# F1C100s.net
KiCad netlist of a schematic drawn in Altium Designer
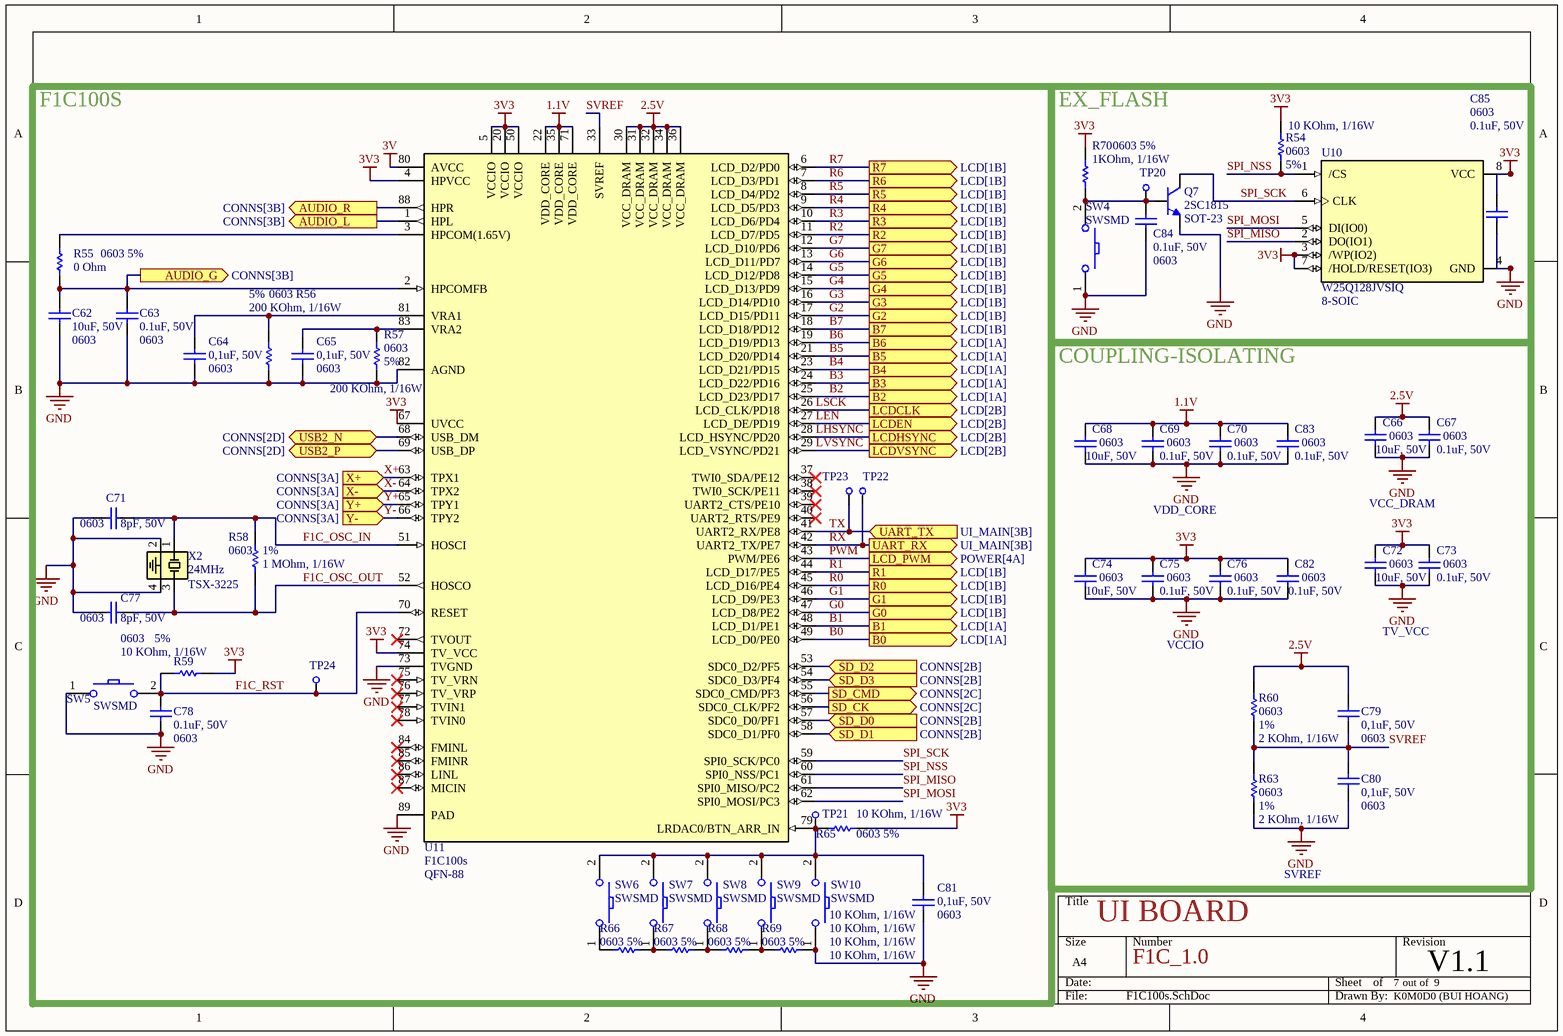
[diagram p0: F1C100s.SchDoc]

(export (version "E")
  (design (tool "Eeschema 10.0.6"))
  (components
    (comp (ref "C62")
      (value "10uF, 50V")
      (footprint "C_0603")
      (description "CAP_0603")
      (fields (field (name "PACKAGE") "0603"))
      (libsource (lib "DisplayLib") (part "CAP_0603"))
    )
    (comp (ref "C63")
      (value "0.1uF, 50V")
      (footprint "C_0603")
      (description "CAP_0603")
      (fields (field (name "PACKAGE") "0603"))
      (libsource (lib "DisplayLib") (part "CAP_0603"))
    )
    (comp (ref "C64")
      (value "0,1uF, 50V")
      (footprint "C_0603")
      (description "CAP_0603")
      (fields (field (name "PACKAGE") "0603"))
      (libsource (lib "DisplayLib") (part "CAP_0603"))
    )
    (comp (ref "C65")
      (value "0,1uF, 50V")
      (footprint "C_0603")
      (description "CAP_0603")
      (fields (field (name "PACKAGE") "0603"))
      (libsource (lib "DisplayLib") (part "CAP_0603"))
    )
    (comp (ref "C66")
      (value "10uF, 50V")
      (footprint "C_0603")
      (description "CAP_0603")
      (fields (field (name "PACKAGE") "0603"))
      (libsource (lib "DisplayLib") (part "CAP_0603"))
    )
    (comp (ref "C67")
      (value "0.1uF, 50V")
      (footprint "C_0603")
      (description "CAP_0603")
      (fields (field (name "PACKAGE") "0603"))
      (libsource (lib "DisplayLib") (part "CAP_0603"))
    )
    (comp (ref "C68")
      (value "10uF, 50V")
      (footprint "C_0603")
      (description "CAP_0603")
      (fields (field (name "PACKAGE") "0603"))
      (libsource (lib "DisplayLib") (part "CAP_0603"))
    )
    (comp (ref "C69")
      (value "0.1uF, 50V")
      (footprint "C_0603")
      (description "CAP_0603")
      (fields (field (name "PACKAGE") "0603"))
      (libsource (lib "DisplayLib") (part "CAP_0603"))
    )
    (comp (ref "C70")
      (value "0.1uF, 50V")
      (footprint "C_0603")
      (description "CAP_0603")
      (fields (field (name "PACKAGE") "0603"))
      (libsource (lib "DisplayLib") (part "CAP_0603"))
    )
    (comp (ref "C71")
      (value "8pF, 50V")
      (footprint "C_0603")
      (description "CAP_0603")
      (fields (field (name "PACKAGE") "0603"))
      (libsource (lib "DisplayLib") (part "CAP_0603"))
    )
    (comp (ref "C72")
      (value "10uF, 50V")
      (footprint "C_0603")
      (description "CAP_0603")
      (fields (field (name "PACKAGE") "0603"))
      (libsource (lib "DisplayLib") (part "CAP_0603"))
    )
    (comp (ref "C73")
      (value "0.1uF, 50V")
      (footprint "C_0603")
      (description "CAP_0603")
      (fields (field (name "PACKAGE") "0603"))
      (libsource (lib "DisplayLib") (part "CAP_0603"))
    )
    (comp (ref "C74")
      (value "10uF, 50V")
      (footprint "C_0603")
      (description "CAP_0603")
      (fields (field (name "PACKAGE") "0603"))
      (libsource (lib "DisplayLib") (part "CAP_0603"))
    )
    (comp (ref "C75")
      (value "0.1uF, 50V")
      (footprint "C_0603")
      (description "CAP_0603")
      (fields (field (name "PACKAGE") "0603"))
      (libsource (lib "DisplayLib") (part "CAP_0603"))
    )
    (comp (ref "C76")
      (value "0.1uF, 50V")
      (footprint "C_0603")
      (description "CAP_0603")
      (fields (field (name "PACKAGE") "0603"))
      (libsource (lib "DisplayLib") (part "CAP_0603"))
    )
    (comp (ref "C77")
      (value "8pF, 50V")
      (footprint "C_0603")
      (description "CAP_0603")
      (fields (field (name "PACKAGE") "0603"))
      (libsource (lib "DisplayLib") (part "CAP_0603"))
    )
    (comp (ref "C78")
      (value "0.1uF, 50V")
      (footprint "C_0603")
      (description "CAP_0603")
      (fields (field (name "PACKAGE") "0603"))
      (libsource (lib "DisplayLib") (part "CAP_0603"))
    )
    (comp (ref "C79")
      (value "0,1uF, 50V")
      (footprint "C_0603")
      (description "CAP_0603")
      (fields (field (name "PACKAGE") "0603"))
      (libsource (lib "DisplayLib") (part "CAP_0603"))
    )
    (comp (ref "C80")
      (value "0,1uF, 50V")
      (footprint "C_0603")
      (description "CAP_0603")
      (fields (field (name "PACKAGE") "0603"))
      (libsource (lib "DisplayLib") (part "CAP_0603"))
    )
    (comp (ref "C81")
      (value "0,1uF, 50V")
      (footprint "C_0603")
      (description "CAP_0603")
      (fields (field (name "PACKAGE") "0603"))
      (libsource (lib "DisplayLib") (part "CAP_0603"))
    )
    (comp (ref "C82")
      (value "0.1uF, 50V")
      (footprint "C_0603")
      (description "CAP_0603")
      (fields (field (name "PACKAGE") "0603"))
      (libsource (lib "DisplayLib") (part "CAP_0603"))
    )
    (comp (ref "C83")
      (value "0.1uF, 50V")
      (footprint "C_0603")
      (description "CAP_0603")
      (fields (field (name "PACKAGE") "0603"))
      (libsource (lib "DisplayLib") (part "CAP_0603"))
    )
    (comp (ref "C84")
      (value "0.1uF, 50V")
      (footprint "C_0603")
      (description "CAP_0603")
      (fields (field (name "PACKAGE") "0603"))
      (libsource (lib "DisplayLib") (part "CAP_0603"))
    )
    (comp (ref "C85")
      (value "0.1uF, 50V")
      (footprint "C_0603")
      (description "CAP_0603")
      (fields (field (name "PACKAGE") "0603"))
      (libsource (lib "DisplayLib") (part "CAP_0603"))
    )
    (comp (ref "Q7")
      (value "2SC1815")
      (footprint "PKG_SOT-23")
      (description "HF Transistor NPN")
      (fields (field (name "PACKAGE") "SOT-23"))
      (libsource (lib "DisplayLib") (part "2SC1815"))
    )
    (comp (ref "R54")
      (value "10 KOhm, 1/16W")
      (footprint "R_0603")
      (description "RES_0603")
      (fields (field (name "PACKAGE") "0603") (field (name "ACC") "5%"))
      (libsource (lib "DisplayLib") (part "RES_0603"))
    )
    (comp (ref "R55")
      (value "0 Ohm")
      (footprint "R_0603")
      (description "RES_0603")
      (fields (field (name "PACKAGE") "0603") (field (name "ACC") "5%"))
      (libsource (lib "DisplayLib") (part "RES_0603"))
    )
    (comp (ref "R56")
      (value "200 KOhm, 1/16W")
      (footprint "R_0603")
      (description "RES_0603")
      (fields (field (name "PACKAGE") "0603") (field (name "ACC") "5%"))
      (libsource (lib "DisplayLib") (part "RES_0603"))
    )
    (comp (ref "R57")
      (value "200 KOhm, 1/16W")
      (footprint "R_0603")
      (description "RES_0603")
      (fields (field (name "PACKAGE") "0603") (field (name "ACC") "5%"))
      (libsource (lib "DisplayLib") (part "RES_0603"))
    )
    (comp (ref "R58")
      (value "1 MOhm, 1/16W")
      (footprint "R_0603")
      (description "RES_0603")
      (fields (field (name "PACKAGE") "0603") (field (name "ACC") "1%"))
      (libsource (lib "DisplayLib") (part "RES_0603"))
    )
    (comp (ref "R59")
      (value "10 KOhm, 1/16W")
      (footprint "R_0603")
      (description "RES_0603")
      (fields (field (name "PACKAGE") "0603") (field (name "ACC") "5%"))
      (libsource (lib "DisplayLib") (part "RES_0603"))
    )
    (comp (ref "R60")
      (value "2 KOhm, 1/16W")
      (footprint "R_0603")
      (description "RES_0603")
      (fields (field (name "PACKAGE") "0603") (field (name "ACC") "1%"))
      (libsource (lib "DisplayLib") (part "RES_0603"))
    )
    (comp (ref "R63")
      (value "2 KOhm, 1/16W")
      (footprint "R_0603")
      (description "RES_0603")
      (fields (field (name "PACKAGE") "0603") (field (name "ACC") "1%"))
      (libsource (lib "DisplayLib") (part "RES_0603"))
    )
    (comp (ref "R65")
      (value "10 KOhm, 1/16W")
      (footprint "R_0603")
      (description "RES_0603")
      (fields (field (name "PACKAGE") "0603") (field (name "ACC") "5%"))
      (libsource (lib "DisplayLib") (part "RES_0603"))
    )
    (comp (ref "R66")
      (value "10 KOhm, 1/16W")
      (footprint "R_0603")
      (description "RES_0603")
      (fields (field (name "PACKAGE") "0603") (field (name "ACC") "5%"))
      (libsource (lib "DisplayLib") (part "RES_0603"))
    )
    (comp (ref "R67")
      (value "10 KOhm, 1/16W")
      (footprint "R_0603")
      (description "RES_0603")
      (fields (field (name "PACKAGE") "0603") (field (name "ACC") "5%"))
      (libsource (lib "DisplayLib") (part "RES_0603"))
    )
    (comp (ref "R68")
      (value "10 KOhm, 1/16W")
      (footprint "R_0603")
      (description "RES_0603")
      (fields (field (name "PACKAGE") "0603") (field (name "ACC") "5%"))
      (libsource (lib "DisplayLib") (part "RES_0603"))
    )
    (comp (ref "R69")
      (value "10 KOhm, 1/16W")
      (footprint "R_0603")
      (description "RES_0603")
      (fields (field (name "PACKAGE") "0603") (field (name "ACC") "5%"))
      (libsource (lib "DisplayLib") (part "RES_0603"))
    )
    (comp (ref "R70")
      (value "1KOhm, 1/16W")
      (footprint "R_0603")
      (description "RES_0603")
      (fields (field (name "PACKAGE") "0603") (field (name "ACC") "5%"))
      (libsource (lib "DisplayLib") (part "RES_0603"))
    )
    (comp (ref "SW4")
      (value "SWSMD")
      (footprint "SW_SMD_NOGND")
      (description "SW_SMD")
      (libsource (lib "DisplayLib") (part "SWSMD_NOGND"))
    )
    (comp (ref "SW5")
      (value "SWSMD")
      (footprint "SW_SMD_NOGND")
      (description "SW_SMD")
      (libsource (lib "") (part "SWSMD_NOGND_1"))
    )
    (comp (ref "SW6")
      (value "SWSMD")
      (footprint "SW_SMD_NOGND")
      (description "SW_SMD")
      (libsource (lib "DisplayLib") (part "SWSMD_NOGND"))
    )
    (comp (ref "SW7")
      (value "SWSMD")
      (footprint "SW_SMD_NOGND")
      (description "SW_SMD")
      (libsource (lib "DisplayLib") (part "SWSMD_NOGND"))
    )
    (comp (ref "SW8")
      (value "SWSMD")
      (footprint "SW_SMD_NOGND")
      (description "SW_SMD")
      (libsource (lib "DisplayLib") (part "SWSMD_NOGND"))
    )
    (comp (ref "SW9")
      (value "SWSMD")
      (footprint "SW_SMD_NOGND")
      (description "SW_SMD")
      (libsource (lib "DisplayLib") (part "SWSMD_NOGND"))
    )
    (comp (ref "SW10")
      (value "SWSMD")
      (footprint "SW_SMD_NOGND")
      (description "SW_SMD")
      (libsource (lib "DisplayLib") (part "SWSMD_NOGND"))
    )
    (comp (ref "TP20")
      (value "TESTPT")
      (footprint "TESTPT")
      (description "Test point")
      (libsource (lib "DisplayLib") (part "TESTPT"))
    )
    (comp (ref "TP21")
      (value "TESTPT")
      (footprint "TESTPT")
      (description "Test point")
      (libsource (lib "DisplayLib") (part "TESTPT"))
    )
    (comp (ref "TP22")
      (value "TESTPT")
      (footprint "TESTPT")
      (description "Test point")
      (libsource (lib "DisplayLib") (part "TESTPT"))
    )
    (comp (ref "TP23")
      (value "TESTPT")
      (footprint "TESTPT")
      (description "Test point")
      (libsource (lib "DisplayLib") (part "TESTPT"))
    )
    (comp (ref "TP24")
      (value "TESTPT")
      (footprint "TESTPT")
      (description "Test point")
      (libsource (lib "DisplayLib") (part "TESTPT"))
    )
    (comp (ref "U10")
      (value "W25Q128JVSIQ")
      (footprint "PKG_8-SOIC")
      (description "FLASH - NOR Memory IC 128Mb (16M x 8) SPI - Quad I/O, QPI, DTR 133 MHz 8-SOIC")
      (fields (field (name "PACKAGE") "8-SOIC"))
      (libsource (lib "DisplayLib") (part "W25Q128JVSIQ"))
    )
    (comp (ref "U11")
      (value "F1C100s")
      (footprint "PKG_QFN-88")
      (fields (field (name "PACKAGE") "QFN-88"))
      (libsource (lib "DisplayLib") (part "F1C100s"))
    )
    (comp (ref "X2")
      (value "24MHz")
      (footprint "PKG_TSX-3225")
      (description "Crystal, 24 MHz, -30 to 85 degC, 3.2 x 2.5 x 0.9 mm SMD")
      (fields (field (name "PACKAGE") "TSX-3225"))
      (libsource (lib "DisplayLib") (part "XTAL"))
    )
  )
  (nets
    (net (code "1") (name "/AUDIO_G") (class "Default")
      (node (ref "C62") (pin "2") (pinfunction "2_2") (pintype "passive"))
      (node (ref "C63") (pin "2") (pinfunction "2_2") (pintype "passive"))
      (node (ref "R55") (pin "1") (pinfunction "1_1") (pintype "passive"))
      (node (ref "U11") (pin "2") (pinfunction "HPCOMFB_2") (pintype "input"))
    )
    (net (code "2") (name "/AUDIO_L") (class "Default")
      (node (ref "U11") (pin "1") (pinfunction "HPL_1") (pintype "output"))
    )
    (net (code "3") (name "/AUDIO_R") (class "Default")
      (node (ref "U11") (pin "88") (pinfunction "HPR_88") (pintype "output"))
    )
    (net (code "4") (name "/B0") (class "Default")
      (node (ref "U11") (pin "49") (pinfunction "LCD_D0/PE0_49") (pintype "bidirectional"))
    )
    (net (code "5") (name "/B1") (class "Default")
      (node (ref "U11") (pin "48") (pinfunction "LCD_D1/PE1_48") (pintype "bidirectional"))
    )
    (net (code "6") (name "/B2") (class "Default")
      (node (ref "U11") (pin "25") (pinfunction "LCD_D23/PD17_25") (pintype "bidirectional"))
    )
    (net (code "7") (name "/B3") (class "Default")
      (node (ref "U11") (pin "24") (pinfunction "LCD_D22/PD16_24") (pintype "bidirectional"))
    )
    (net (code "8") (name "/B4") (class "Default")
      (node (ref "U11") (pin "23") (pinfunction "LCD_D21/PD15_23") (pintype "bidirectional"))
    )
    (net (code "9") (name "/B5") (class "Default")
      (node (ref "U11") (pin "21") (pinfunction "LCD_D20/PD14_21") (pintype "bidirectional"))
    )
    (net (code "10") (name "/B6") (class "Default")
      (node (ref "U11") (pin "19") (pinfunction "LCD_D19/PD13_19") (pintype "bidirectional"))
    )
    (net (code "11") (name "/B7") (class "Default")
      (node (ref "U11") (pin "18") (pinfunction "LCD_D18/PD12_18") (pintype "bidirectional"))
    )
    (net (code "12") (name "/F1C_OSC_IN") (class "Default")
      (node (ref "C71") (pin "2") (pinfunction "2_2") (pintype "passive"))
      (node (ref "R58") (pin "2") (pinfunction "2_2") (pintype "passive"))
      (node (ref "U11") (pin "51") (pinfunction "HOSCI_51") (pintype "input"))
      (node (ref "X2") (pin "1") (pinfunction "1_1") (pintype "passive"))
    )
    (net (code "13") (name "/F1C_OSC_OUT") (class "Default")
      (node (ref "C77") (pin "2") (pinfunction "2_2") (pintype "passive"))
      (node (ref "R58") (pin "1") (pinfunction "1_1") (pintype "passive"))
      (node (ref "U11") (pin "52") (pinfunction "HOSCO_52") (pintype "output"))
      (node (ref "X2") (pin "3") (pinfunction "3_3") (pintype "passive"))
    )
    (net (code "14") (name "/F1C_RST") (class "Default")
      (node (ref "C78") (pin "2") (pinfunction "2_2") (pintype "passive"))
      (node (ref "R59") (pin "1") (pinfunction "1_1") (pintype "passive"))
      (node (ref "SW5") (pin "2") (pinfunction "2_2") (pintype "passive"))
      (node (ref "TP24") (pin "1") (pinfunction "1_1") (pintype "passive"))
      (node (ref "U11") (pin "70") (pinfunction "RESET_70") (pintype "bidirectional"))
    )
    (net (code "15") (name "/G0") (class "Default")
      (node (ref "U11") (pin "47") (pinfunction "LCD_D8/PE2_47") (pintype "bidirectional"))
    )
    (net (code "16") (name "/G1") (class "Default")
      (node (ref "U11") (pin "46") (pinfunction "LCD_D9/PE3_46") (pintype "bidirectional"))
    )
    (net (code "17") (name "/G2") (class "Default")
      (node (ref "U11") (pin "17") (pinfunction "LCD_D15/PD11_17") (pintype "bidirectional"))
    )
    (net (code "18") (name "/G3") (class "Default")
      (node (ref "U11") (pin "16") (pinfunction "LCD_D14/PD10_16") (pintype "bidirectional"))
    )
    (net (code "19") (name "/G4") (class "Default")
      (node (ref "U11") (pin "15") (pinfunction "LCD_D13/PD9_15") (pintype "bidirectional"))
    )
    (net (code "20") (name "/G5") (class "Default")
      (node (ref "U11") (pin "14") (pinfunction "LCD_D12/PD8_14") (pintype "bidirectional"))
    )
    (net (code "21") (name "/G6") (class "Default")
      (node (ref "U11") (pin "13") (pinfunction "LCD_D11/PD7_13") (pintype "bidirectional"))
    )
    (net (code "22") (name "/G7") (class "Default")
      (node (ref "U11") (pin "12") (pinfunction "LCD_D10/PD6_12") (pintype "bidirectional"))
    )
    (net (code "23") (name "/LEN") (class "Default")
      (node (ref "U11") (pin "27") (pinfunction "LCD_DE/PD19_27") (pintype "bidirectional"))
    )
    (net (code "24") (name "/LHSYNC") (class "Default")
      (node (ref "U11") (pin "28") (pinfunction "LCD_HSYNC/PD20_28") (pintype "bidirectional"))
    )
    (net (code "25") (name "/LSCK") (class "Default")
      (node (ref "U11") (pin "26") (pinfunction "LCD_CLK/PD18_26") (pintype "bidirectional"))
    )
    (net (code "26") (name "/LVSYNC") (class "Default")
      (node (ref "U11") (pin "29") (pinfunction "LCD_VSYNC/PD21_29") (pintype "bidirectional"))
    )
    (net (code "27") (name "/PWM") (class "Default")
      (node (ref "U11") (pin "43") (pinfunction "PWM/PE6_43") (pintype "bidirectional"))
    )
    (net (code "28") (name "/R0") (class "Default")
      (node (ref "U11") (pin "45") (pinfunction "LCD_D16/PE4_45") (pintype "bidirectional"))
    )
    (net (code "29") (name "/R1") (class "Default")
      (node (ref "U11") (pin "44") (pinfunction "LCD_D17/PE5_44") (pintype "bidirectional"))
    )
    (net (code "30") (name "/R2") (class "Default")
      (node (ref "U11") (pin "11") (pinfunction "LCD_D7/PD5_11") (pintype "bidirectional"))
    )
    (net (code "31") (name "/R3") (class "Default")
      (node (ref "U11") (pin "10") (pinfunction "LCD_D6/PD4_10") (pintype "bidirectional"))
    )
    (net (code "32") (name "/R4") (class "Default")
      (node (ref "U11") (pin "9") (pinfunction "LCD_D5/PD3_9") (pintype "bidirectional"))
    )
    (net (code "33") (name "/R5") (class "Default")
      (node (ref "U11") (pin "8") (pinfunction "LCD_D4/PD2_8") (pintype "bidirectional"))
    )
    (net (code "34") (name "/R6") (class "Default")
      (node (ref "U11") (pin "7") (pinfunction "LCD_D3/PD1_7") (pintype "bidirectional"))
    )
    (net (code "35") (name "/R7") (class "Default")
      (node (ref "U11") (pin "6") (pinfunction "LCD_D2/PD0_6") (pintype "bidirectional"))
    )
    (net (code "36") (name "/RX") (class "Default")
      (node (ref "TP22") (pin "1") (pinfunction "1_1") (pintype "passive"))
      (node (ref "U11") (pin "42") (pinfunction "UART2_TX/PE7_42") (pintype "bidirectional"))
    )
    (net (code "37") (name "/SD_CK") (class "Default")
      (node (ref "U11") (pin "56") (pinfunction "SDC0_CLK/PF2_56") (pintype "bidirectional"))
    )
    (net (code "38") (name "/SD_CMD") (class "Default")
      (node (ref "U11") (pin "55") (pinfunction "SDC0_CMD/PF3_55") (pintype "bidirectional"))
    )
    (net (code "39") (name "/SD_D0") (class "Default")
      (node (ref "U11") (pin "57") (pinfunction "SDC0_D0/PF1_57") (pintype "bidirectional"))
    )
    (net (code "40") (name "/SD_D1") (class "Default")
      (node (ref "U11") (pin "58") (pinfunction "SDC0_D1/PF0_58") (pintype "bidirectional"))
    )
    (net (code "41") (name "/SD_D2") (class "Default")
      (node (ref "U11") (pin "53") (pinfunction "SDC0_D2/PF5_53") (pintype "bidirectional"))
    )
    (net (code "42") (name "/SD_D3") (class "Default")
      (node (ref "U11") (pin "54") (pinfunction "SDC0_D3/PF4_54") (pintype "bidirectional"))
    )
    (net (code "43") (name "/SPI_MISO") (class "Default")
      (node (ref "U10") (pin "2") (pinfunction "DO(IO1)_2") (pintype "bidirectional"))
      (node (ref "U11") (pin "61") (pinfunction "SPI0_MISO/PC2_61") (pintype "bidirectional"))
    )
    (net (code "44") (name "/SPI_MOSI") (class "Default")
      (node (ref "U10") (pin "5") (pinfunction "DI(IO0)_5") (pintype "bidirectional"))
      (node (ref "U11") (pin "62") (pinfunction "SPI0_MOSI/PC3_62") (pintype "bidirectional"))
    )
    (net (code "45") (name "/SPI_NSS") (class "Default")
      (node (ref "R54") (pin "1") (pinfunction "1_1") (pintype "passive"))
      (node (ref "U10") (pin "1") (pinfunction "/CS_1") (pintype "input"))
      (node (ref "U11") (pin "60") (pinfunction "SPI0_NSS/PC1_60") (pintype "bidirectional"))
    )
    (net (code "46") (name "/SPI_SCK") (class "Default")
      (node (ref "Q7") (pin "3") (pinfunction "C_3") (pintype "passive"))
      (node (ref "U10") (pin "6") (pinfunction "CLK_6") (pintype "input"))
      (node (ref "U11") (pin "59") (pinfunction "SPI0_SCK/PC0_59") (pintype "bidirectional"))
    )
    (net (code "47") (name "/SVREF") (class "Default")
      (node (ref "C79") (pin "1") (pinfunction "1_1") (pintype "passive"))
      (node (ref "C80") (pin "2") (pinfunction "2_2") (pintype "passive"))
      (node (ref "R60") (pin "1") (pinfunction "1_1") (pintype "passive"))
      (node (ref "R63") (pin "2") (pinfunction "2_2") (pintype "passive"))
      (node (ref "U11") (pin "33") (pinfunction "SVREF_33") (pintype "power_in"))
    )
    (net (code "48") (name "/TX") (class "Default")
      (node (ref "TP23") (pin "1") (pinfunction "1_1") (pintype "passive"))
      (node (ref "U11") (pin "41") (pinfunction "UART2_RX/PE8_41") (pintype "bidirectional"))
    )
    (net (code "49") (name "/USB2_N") (class "Default")
      (node (ref "U11") (pin "68") (pinfunction "USB_DM_68") (pintype "bidirectional"))
    )
    (net (code "50") (name "/USB2_P") (class "Default")
      (node (ref "U11") (pin "69") (pinfunction "USB_DP_69") (pintype "bidirectional"))
    )
    (net (code "51") (name "/X+") (class "Default")
      (node (ref "U11") (pin "63") (pinfunction "TPX1_63") (pintype "bidirectional"))
    )
    (net (code "52") (name "/X-") (class "Default")
      (node (ref "U11") (pin "64") (pinfunction "TPX2_64") (pintype "bidirectional"))
    )
    (net (code "53") (name "/Y+") (class "Default")
      (node (ref "U11") (pin "65") (pinfunction "TPY1_65") (pintype "bidirectional"))
    )
    (net (code "54") (name "/Y-") (class "Default")
      (node (ref "U11") (pin "66") (pinfunction "TPY2_66") (pintype "bidirectional"))
    )
    (net (code "55") (name "1.1V") (class "Default")
      (node (ref "C68") (pin "2") (pinfunction "2_2") (pintype "passive"))
      (node (ref "C69") (pin "2") (pinfunction "2_2") (pintype "passive"))
      (node (ref "C70") (pin "2") (pinfunction "2_2") (pintype "passive"))
      (node (ref "C83") (pin "2") (pinfunction "2_2") (pintype "passive"))
      (node (ref "U11") (pin "22") (pinfunction "VDD_CORE_22") (pintype "power_in"))
      (node (ref "U11") (pin "35") (pinfunction "VDD_CORE_35") (pintype "power_in"))
      (node (ref "U11") (pin "71") (pinfunction "VDD_CORE_71") (pintype "power_in"))
    )
    (net (code "56") (name "2.5V") (class "Default")
      (node (ref "C66") (pin "2") (pinfunction "2_2") (pintype "passive"))
      (node (ref "C67") (pin "2") (pinfunction "2_2") (pintype "passive"))
      (node (ref "C79") (pin "2") (pinfunction "2_2") (pintype "passive"))
      (node (ref "R60") (pin "2") (pinfunction "2_2") (pintype "passive"))
      (node (ref "U11") (pin "30") (pinfunction "VCC_DRAM_30") (pintype "power_in"))
      (node (ref "U11") (pin "31") (pinfunction "VCC_DRAM_31") (pintype "power_in"))
      (node (ref "U11") (pin "32") (pinfunction "VCC_DRAM_32") (pintype "power_in"))
      (node (ref "U11") (pin "34") (pinfunction "VCC_DRAM_34") (pintype "power_in"))
      (node (ref "U11") (pin "36") (pinfunction "VCC_DRAM_36") (pintype "power_in"))
    )
    (net (code "57") (name "3V") (class "Default")
      (node (ref "U11") (pin "80") (pinfunction "AVCC_80") (pintype "power_in"))
    )
    (net (code "58") (name "3V3") (class "Default")
      (node (ref "C72") (pin "2") (pinfunction "2_2") (pintype "passive"))
      (node (ref "C73") (pin "2") (pinfunction "2_2") (pintype "passive"))
      (node (ref "C74") (pin "2") (pinfunction "2_2") (pintype "passive"))
      (node (ref "C75") (pin "2") (pinfunction "2_2") (pintype "passive"))
      (node (ref "C76") (pin "2") (pinfunction "2_2") (pintype "passive"))
      (node (ref "C82") (pin "2") (pinfunction "2_2") (pintype "passive"))
      (node (ref "C85") (pin "2") (pinfunction "2_2") (pintype "passive"))
      (node (ref "R54") (pin "2") (pinfunction "2_2") (pintype "passive"))
      (node (ref "R59") (pin "2") (pinfunction "2_2") (pintype "passive"))
      (node (ref "R65") (pin "2") (pinfunction "2_2") (pintype "passive"))
      (node (ref "R70") (pin "2") (pinfunction "2_2") (pintype "passive"))
      (node (ref "U10") (pin "3") (pinfunction "/WP(IO2)_3") (pintype "bidirectional"))
      (node (ref "U10") (pin "7") (pinfunction "/HOLD/RESET(IO3)_7") (pintype "bidirectional"))
      (node (ref "U10") (pin "8") (pinfunction "VCC_8") (pintype "power_in"))
      (node (ref "U11") (pin "20") (pinfunction "VCCIO_20") (pintype "power_in"))
      (node (ref "U11") (pin "4") (pinfunction "HPVCC_4") (pintype "power_in"))
      (node (ref "U11") (pin "5") (pinfunction "VCCIO_5") (pintype "power_in"))
      (node (ref "U11") (pin "50") (pinfunction "VCCIO_50") (pintype "power_in"))
      (node (ref "U11") (pin "67") (pinfunction "UVCC_67") (pintype "power_in"))
      (node (ref "U11") (pin "74") (pinfunction "TV_VCC_74") (pintype "power_in"))
    )
    (net (code "59") (name "GND") (class "Default")
      (node (ref "C62") (pin "1") (pinfunction "1_1") (pintype "passive"))
      (node (ref "C63") (pin "1") (pinfunction "1_1") (pintype "passive"))
      (node (ref "C64") (pin "1") (pinfunction "1_1") (pintype "passive"))
      (node (ref "C65") (pin "1") (pinfunction "1_1") (pintype "passive"))
      (node (ref "C66") (pin "1") (pinfunction "1_1") (pintype "passive"))
      (node (ref "C67") (pin "1") (pinfunction "1_1") (pintype "passive"))
      (node (ref "C68") (pin "1") (pinfunction "1_1") (pintype "passive"))
      (node (ref "C69") (pin "1") (pinfunction "1_1") (pintype "passive"))
      (node (ref "C70") (pin "1") (pinfunction "1_1") (pintype "passive"))
      (node (ref "C71") (pin "1") (pinfunction "1_1") (pintype "passive"))
      (node (ref "C72") (pin "1") (pinfunction "1_1") (pintype "passive"))
      (node (ref "C73") (pin "1") (pinfunction "1_1") (pintype "passive"))
      (node (ref "C74") (pin "1") (pinfunction "1_1") (pintype "passive"))
      (node (ref "C75") (pin "1") (pinfunction "1_1") (pintype "passive"))
      (node (ref "C76") (pin "1") (pinfunction "1_1") (pintype "passive"))
      (node (ref "C77") (pin "1") (pinfunction "1_1") (pintype "passive"))
      (node (ref "C78") (pin "1") (pinfunction "1_1") (pintype "passive"))
      (node (ref "C80") (pin "1") (pinfunction "1_1") (pintype "passive"))
      (node (ref "C81") (pin "1") (pinfunction "1_1") (pintype "passive"))
      (node (ref "C82") (pin "1") (pinfunction "1_1") (pintype "passive"))
      (node (ref "C83") (pin "1") (pinfunction "1_1") (pintype "passive"))
      (node (ref "C84") (pin "1") (pinfunction "1_1") (pintype "passive"))
      (node (ref "C85") (pin "1") (pinfunction "1_1") (pintype "passive"))
      (node (ref "Q7") (pin "2") (pinfunction "E_2") (pintype "passive"))
      (node (ref "R56") (pin "1") (pinfunction "1_1") (pintype "passive"))
      (node (ref "R57") (pin "1") (pinfunction "1_1") (pintype "passive"))
      (node (ref "R63") (pin "1") (pinfunction "1_1") (pintype "passive"))
      (node (ref "R69") (pin "2") (pinfunction "2_2") (pintype "passive"))
      (node (ref "SW10") (pin "1") (pinfunction "1_1") (pintype "passive"))
      (node (ref "SW4") (pin "1") (pinfunction "1_1") (pintype "passive"))
      (node (ref "SW5") (pin "1") (pinfunction "1_1") (pintype "passive"))
      (node (ref "U10") (pin "4") (pinfunction "GND_4") (pintype "power_in"))
      (node (ref "U11") (pin "73") (pinfunction "TVGND_73") (pintype "power_in"))
      (node (ref "U11") (pin "82") (pinfunction "AGND_82") (pintype "power_in"))
      (node (ref "U11") (pin "89") (pinfunction "PAD_89") (pintype "passive"))
      (node (ref "X2") (pin "2") (pinfunction "2_2") (pintype "passive"))
      (node (ref "X2") (pin "4") (pinfunction "4_4") (pintype "passive"))
    )
    (net (code "60") (name "Net-(Q7-B)") (class "Default")
      (node (ref "C84") (pin "2") (pinfunction "2_2") (pintype "passive"))
      (node (ref "Q7") (pin "1") (pinfunction "B_1") (pintype "passive"))
      (node (ref "R70") (pin "1") (pinfunction "1_1") (pintype "passive"))
      (node (ref "SW4") (pin "2") (pinfunction "2_2") (pintype "passive"))
      (node (ref "TP20") (pin "1") (pinfunction "1_1") (pintype "passive"))
    )
    (net (code "61") (name "Net-(R66-Pad1)") (class "Default")
      (node (ref "R66") (pin "1") (pinfunction "1_1") (pintype "passive"))
      (node (ref "SW6") (pin "1") (pinfunction "1_1") (pintype "passive"))
    )
    (net (code "62") (name "Net-(R66-Pad2)") (class "Default")
      (node (ref "R66") (pin "2") (pinfunction "2_2") (pintype "passive"))
      (node (ref "R67") (pin "1") (pinfunction "1_1") (pintype "passive"))
      (node (ref "SW7") (pin "1") (pinfunction "1_1") (pintype "passive"))
    )
    (net (code "63") (name "Net-(R67-Pad2)") (class "Default")
      (node (ref "R67") (pin "2") (pinfunction "2_2") (pintype "passive"))
      (node (ref "R68") (pin "1") (pinfunction "1_1") (pintype "passive"))
      (node (ref "SW8") (pin "1") (pinfunction "1_1") (pintype "passive"))
    )
    (net (code "64") (name "Net-(R68-Pad2)") (class "Default")
      (node (ref "R68") (pin "2") (pinfunction "2_2") (pintype "passive"))
      (node (ref "R69") (pin "1") (pinfunction "1_1") (pintype "passive"))
      (node (ref "SW9") (pin "1") (pinfunction "1_1") (pintype "passive"))
    )
    (net (code "65") (name "Net-(U11-HPCOM(1.65V))") (class "Default")
      (node (ref "R55") (pin "2") (pinfunction "2_2") (pintype "passive"))
      (node (ref "U11") (pin "3") (pinfunction "HPCOM(1.65V)_3") (pintype "power_in"))
    )
    (net (code "66") (name "Net-(U11-LRDAC0{slash}BTN_ARR_IN)") (class "Default")
      (node (ref "C81") (pin "2") (pinfunction "2_2") (pintype "passive"))
      (node (ref "R65") (pin "1") (pinfunction "1_1") (pintype "passive"))
      (node (ref "SW10") (pin "2") (pinfunction "2_2") (pintype "passive"))
      (node (ref "SW6") (pin "2") (pinfunction "2_2") (pintype "passive"))
      (node (ref "SW7") (pin "2") (pinfunction "2_2") (pintype "passive"))
      (node (ref "SW8") (pin "2") (pinfunction "2_2") (pintype "passive"))
      (node (ref "SW9") (pin "2") (pinfunction "2_2") (pintype "passive"))
      (node (ref "TP21") (pin "1") (pinfunction "1_1") (pintype "passive"))
      (node (ref "U11") (pin "79") (pinfunction "LRDAC0/BTN_ARR_IN_79") (pintype "input"))
    )
    (net (code "67") (name "Net-(U11-VRA1)") (class "Default")
      (node (ref "C64") (pin "2") (pinfunction "2_2") (pintype "passive"))
      (node (ref "R56") (pin "2") (pinfunction "2_2") (pintype "passive"))
      (node (ref "U11") (pin "81") (pinfunction "VRA1_81") (pintype "passive"))
    )
    (net (code "68") (name "Net-(U11-VRA2)") (class "Default")
      (node (ref "C65") (pin "2") (pinfunction "2_2") (pintype "passive"))
      (node (ref "R57") (pin "2") (pinfunction "2_2") (pintype "passive"))
      (node (ref "U11") (pin "83") (pinfunction "VRA2_83") (pintype "passive"))
    )
    (net (code "69") (name "unconnected-(U11-FMINL-Pad84)") (class "Default")
      (node (ref "U11") (pin "84") (pinfunction "FMINL_84") (pintype "bidirectional+no_connect"))
    )
    (net (code "70") (name "unconnected-(U11-FMINR-Pad85)") (class "Default")
      (node (ref "U11") (pin "85") (pinfunction "FMINR_85") (pintype "bidirectional+no_connect"))
    )
    (net (code "71") (name "unconnected-(U11-LINL-Pad86)") (class "Default")
      (node (ref "U11") (pin "86") (pinfunction "LINL_86") (pintype "bidirectional+no_connect"))
    )
    (net (code "72") (name "unconnected-(U11-MICIN-Pad87)") (class "Default")
      (node (ref "U11") (pin "87") (pinfunction "MICIN_87") (pintype "bidirectional+no_connect"))
    )
    (net (code "73") (name "unconnected-(U11-TVIN0-Pad78)") (class "Default")
      (node (ref "U11") (pin "78") (pinfunction "TVIN0_78") (pintype "input+no_connect"))
    )
    (net (code "74") (name "unconnected-(U11-TVIN1-Pad77)") (class "Default")
      (node (ref "U11") (pin "77") (pinfunction "TVIN1_77") (pintype "input+no_connect"))
    )
    (net (code "75") (name "unconnected-(U11-TVOUT-Pad72)") (class "Default")
      (node (ref "U11") (pin "72") (pinfunction "TVOUT_72") (pintype "output+no_connect"))
    )
    (net (code "76") (name "unconnected-(U11-TV_VRN-Pad75)") (class "Default")
      (node (ref "U11") (pin "75") (pinfunction "TV_VRN_75") (pintype "input+no_connect"))
    )
    (net (code "77") (name "unconnected-(U11-TV_VRP-Pad76)") (class "Default")
      (node (ref "U11") (pin "76") (pinfunction "TV_VRP_76") (pintype "input+no_connect"))
    )
    (net (code "78") (name "unconnected-(U11-TWI0_SCK{slash}PE11-Pad38)") (class "Default")
      (node (ref "U11") (pin "38") (pinfunction "TWI0_SCK/PE11_38") (pintype "bidirectional+no_connect"))
    )
    (net (code "79") (name "unconnected-(U11-TWI0_SDA{slash}PE12-Pad37)") (class "Default")
      (node (ref "U11") (pin "37") (pinfunction "TWI0_SDA/PE12_37") (pintype "bidirectional+no_connect"))
    )
    (net (code "80") (name "unconnected-(U11-UART2_CTS{slash}PE10-Pad39)") (class "Default")
      (node (ref "U11") (pin "39") (pinfunction "UART2_CTS/PE10_39") (pintype "bidirectional+no_connect"))
    )
    (net (code "81") (name "unconnected-(U11-UART2_RTS{slash}PE9-Pad40)") (class "Default")
      (node (ref "U11") (pin "40") (pinfunction "UART2_RTS/PE9_40") (pintype "bidirectional+no_connect"))
    )
  )
)
